# Main2.net
KiCad netlist of a schematic drawn in EAGLE
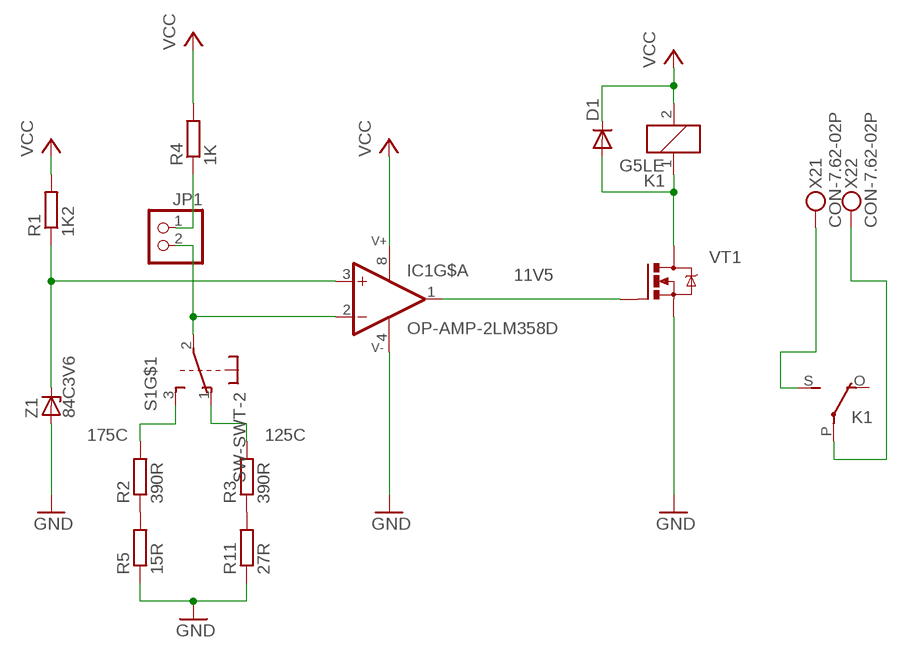
[diagram p0: schematic, sheet 1]
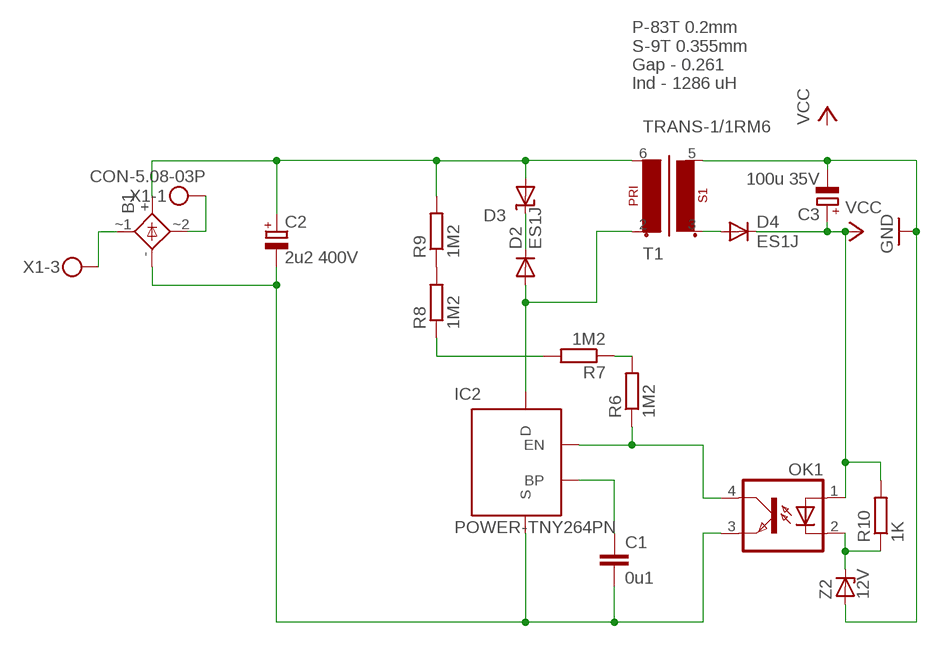
[diagram p1: schematic, sheet 2]

(export (version "E")
  (design (tool "Eeschema 10.0.6"))
  (components
    (comp (ref "D1")
      (value "DIODE_ES1J")
      (footprint "eagle-import:DO214AC")
      (libsource (lib "eagle-import") (part "DIODE_ES1J"))
    )
    (comp (ref "IC1")
      (value "OP-AMP-2LM358D")
      (footprint "eagle-import:SO8")
      (libsource (lib "eagle-import") (part "OP-AMP-2LM358D"))
    )
    (comp (ref "JP1")
      (value "PINHD-1X2")
      (footprint "eagle-import:1X02")
      (libsource (lib "eagle-import") (part "PINHD-1X2"))
    )
    (comp (ref "K1")
      (value "G5LE")
      (footprint "eagle-import:G5LE")
      (libsource (lib "eagle-import") (part "G5LE"))
    )
    (comp (ref "R1")
      (value "1K2")
      (footprint "eagle-import:R1206")
      (libsource (lib "eagle-import") (part "R_1206"))
    )
    (comp (ref "R2")
      (value "390R")
      (footprint "eagle-import:R0805")
      (libsource (lib "eagle-import") (part "R_0805"))
    )
    (comp (ref "R3")
      (value "390R")
      (footprint "eagle-import:R0805")
      (libsource (lib "eagle-import") (part "R_0805"))
    )
    (comp (ref "R4")
      (value "1K")
      (footprint "eagle-import:R1206")
      (libsource (lib "eagle-import") (part "R_1206"))
    )
    (comp (ref "R5")
      (value "15R")
      (footprint "eagle-import:R0805")
      (libsource (lib "eagle-import") (part "R_0805"))
    )
    (comp (ref "R11")
      (value "27R")
      (footprint "eagle-import:R0805")
      (libsource (lib "eagle-import") (part "R_0805"))
    )
    (comp (ref "S1")
      (value "SW-SWT-2")
      (footprint "eagle-import:SWT-2")
      (libsource (lib "eagle-import") (part "SW-SWT-2"))
    )
    (comp (ref "VT1")
      (value "FET-NPF-2X2")
      (footprint "eagle-import:POWERFLAT-2X2")
      (libsource (lib "eagle-import") (part "FET-NPF-2X2"))
    )
    (comp (ref "X2")
      (value "CON-7.62-02P")
      (footprint "eagle-import:KF25C-7.62-02P-13")
      (libsource (lib "eagle-import") (part "CON-7.62-02P"))
    )
    (comp (ref "Z1")
      (value "84C3V6")
      (footprint "eagle-import:SOT23")
      (libsource (lib "eagle-import") (part "ZENER_SOT23"))
    )
    (comp (ref "B1")
      (value "RECTIFIERSOIC-8")
      (footprint "eagle-import:SOIC-4")
      (libsource (lib "eagle-import") (part "RECTIFIERSOIC-8"))
    )
    (comp (ref "C1")
      (value "0u1")
      (footprint "eagle-import:C0805")
      (libsource (lib "eagle-import") (part "CAP_0805"))
    )
    (comp (ref "C2")
      (value "2u2 400V")
      (footprint "eagle-import:E2,5-7")
      (libsource (lib "eagle-import") (part "CAP-POL_E2.5-7"))
    )
    (comp (ref "C3")
      (value "100u 35V")
      (footprint "eagle-import:E3,5-8")
      (libsource (lib "eagle-import") (part "CAP-POL_E3.5-8"))
    )
    (comp (ref "D2")
      (value "ES1J")
      (footprint "eagle-import:DO214AC")
      (libsource (lib "eagle-import") (part "DIODE_ES1J"))
    )
    (comp (ref "D3")
      (value "SUPRESSORDO-204AC")
      (footprint "eagle-import:DO15-12")
      (libsource (lib "eagle-import") (part "SUPRESSORDO-204AC"))
    )
    (comp (ref "D4")
      (value "ES1J")
      (footprint "eagle-import:DO214AC")
      (libsource (lib "eagle-import") (part "DIODE_ES1J"))
    )
    (comp (ref "IC2")
      (value "POWER-TNY264PN")
      (footprint "eagle-import:DIP-8B")
      (libsource (lib "eagle-import") (part "POWER-TNY264PN"))
    )
    (comp (ref "OK1")
      (value "OPTOTRANSPC817")
      (footprint "eagle-import:DIL04")
      (fields (field (name "MPN") "PC817X4J000F"))
      (libsource (lib "eagle-import") (part "OPTOTRANSPC817"))
    )
    (comp (ref "R6")
      (value "1M2")
      (footprint "eagle-import:R0805")
      (libsource (lib "eagle-import") (part "R_0805"))
    )
    (comp (ref "R7")
      (value "1M2")
      (footprint "eagle-import:R0805")
      (libsource (lib "eagle-import") (part "R_0805"))
    )
    (comp (ref "R8")
      (value "1M2")
      (footprint "eagle-import:R0805")
      (libsource (lib "eagle-import") (part "R_0805"))
    )
    (comp (ref "R9")
      (value "1M2")
      (footprint "eagle-import:R0805")
      (libsource (lib "eagle-import") (part "R_0805"))
    )
    (comp (ref "R10")
      (value "1K")
      (footprint "eagle-import:R1206")
      (libsource (lib "eagle-import") (part "R_1206"))
    )
    (comp (ref "T1")
      (value "TRANS-1/1RM6")
      (footprint "eagle-import:RM6")
      (libsource (lib "eagle-import") (part "TRANS-1/1RM6"))
    )
    (comp (ref "X1")
      (value "CON-5.08-03P")
      (footprint "eagle-import:MKDSN1,5_3-5,08")
      (libsource (lib "eagle-import") (part "CON-5.08-03P"))
    )
    (comp (ref "Z2")
      (value "12V")
      (footprint "eagle-import:MINIMELF")
      (libsource (lib "eagle-import") (part "ZENER_MINIMELF"))
    )
  )
  (nets
    (net (code "1") (name "GND") (class "Default")
      (node (ref "C3") (pin "-") (pinfunction "-_-") (pintype "passive"))
      (node (ref "IC1") (pin "4") (pinfunction "V-_4") (pintype "power_in"))
      (node (ref "R11") (pin "1") (pinfunction "1_1") (pintype "passive"))
      (node (ref "R5") (pin "1") (pinfunction "1_1") (pintype "passive"))
      (node (ref "T1") (pin "5") (pinfunction "S1-2_5") (pintype "passive"))
      (node (ref "VT1") (pin "S") (pinfunction "S_S") (pintype "passive"))
      (node (ref "VT1") (pin "S4") (pinfunction "S_S4") (pintype "passive"))
      (node (ref "Z1") (pin "1") (pinfunction "A_1") (pintype "passive"))
      (node (ref "Z2") (pin "A") (pinfunction "A_A") (pintype "passive"))
    )
    (net (code "2") (name "Net-(B1-AC1)") (class "Default")
      (node (ref "B1") (pin "~1") (pinfunction "AC1_~1") (pintype "passive"))
      (node (ref "X1") (pin "3") (pinfunction "KL_3") (pintype "passive"))
    )
    (net (code "3") (name "Net-(B1-AC2)") (class "Default")
      (node (ref "B1") (pin "~2") (pinfunction "AC2_~2") (pintype "passive"))
      (node (ref "X1") (pin "1") (pinfunction "KL_1") (pintype "passive"))
    )
    (net (code "4") (name "Net-(D1-PadA)") (class "Default")
      (node (ref "D1") (pin "A") (pinfunction "A_A") (pintype "passive"))
      (node (ref "K1") (pin "1") (pinfunction "1_1") (pintype "passive"))
      (node (ref "VT1") (pin "D") (pinfunction "D_D") (pintype "passive"))
      (node (ref "VT1") (pin "D1") (pinfunction "D_D1") (pintype "passive"))
      (node (ref "VT1") (pin "D2") (pinfunction "D_D2") (pintype "passive"))
      (node (ref "VT1") (pin "D5") (pinfunction "D_D5") (pintype "passive"))
      (node (ref "VT1") (pin "D6") (pinfunction "D_D6") (pintype "passive"))
    )
    (net (code "5") (name "Net-(D2-PadC)") (class "Default")
      (node (ref "D2") (pin "C") (pinfunction "C_C") (pintype "passive"))
      (node (ref "D3") (pin "C") (pinfunction "C_C") (pintype "passive"))
    )
    (net (code "6") (name "Net-(IC1A-+IN)") (class "Default")
      (node (ref "IC1") (pin "3") (pinfunction "+IN_3") (pintype "input"))
      (node (ref "R1") (pin "1") (pinfunction "1_1") (pintype "passive"))
      (node (ref "Z1") (pin "3") (pinfunction "C_3") (pintype "passive"))
    )
    (net (code "7") (name "Net-(IC1A--IN)") (class "Default")
      (node (ref "IC1") (pin "2") (pinfunction "-IN_2") (pintype "input"))
      (node (ref "JP1") (pin "2") (pinfunction "2_2") (pintype "passive"))
      (node (ref "S1") (pin "2") (pinfunction "2_2") (pintype "passive"))
    )
    (net (code "8") (name "Net-(IC1A-OUT)") (class "Default")
      (node (ref "IC1") (pin "1") (pinfunction "OUT_1") (pintype "output"))
      (node (ref "VT1") (pin "G3") (pinfunction "G_G3") (pintype "passive"))
    )
    (net (code "9") (name "Net-(IC2-BP)") (class "Default")
      (node (ref "C1") (pin "1") (pinfunction "1_1") (pintype "passive"))
      (node (ref "IC2") (pin "1") (pinfunction "BP_1") (pintype "input"))
    )
    (net (code "10") (name "Net-(IC2-D)") (class "Default")
      (node (ref "D2") (pin "A") (pinfunction "A_A") (pintype "passive"))
      (node (ref "IC2") (pin "5") (pinfunction "D_5") (pintype "input"))
      (node (ref "T1") (pin "2") (pinfunction "P1-1_2") (pintype "passive"))
    )
    (net (code "11") (name "Net-(IC2-EN)") (class "Default")
      (node (ref "IC2") (pin "4") (pinfunction "EN_4") (pintype "input"))
      (node (ref "OK1") (pin "4") (pinfunction "COL_4") (pintype "passive"))
      (node (ref "R6") (pin "1") (pinfunction "1_1") (pintype "passive"))
    )
    (net (code "12") (name "Net-(JP1-Pad1)") (class "Default")
      (node (ref "JP1") (pin "1") (pinfunction "1_1") (pintype "passive"))
      (node (ref "R4") (pin "1") (pinfunction "1_1") (pintype "passive"))
    )
    (net (code "13") (name "Net-(OK1-C)") (class "Default")
      (node (ref "OK1") (pin "2") (pinfunction "C_2") (pintype "passive"))
      (node (ref "R10") (pin "1") (pinfunction "1_1") (pintype "passive"))
      (node (ref "Z2") (pin "C") (pinfunction "C_C") (pintype "passive"))
    )
    (net (code "14") (name "Net-(OK1-EMIT)") (class "Default")
      (node (ref "B1") (pin "-") (pinfunction "-_-") (pintype "passive"))
      (node (ref "C1") (pin "2") (pinfunction "2_2") (pintype "passive"))
      (node (ref "C2") (pin "-") (pinfunction "-_-") (pintype "passive"))
      (node (ref "IC2") (pin "2") (pinfunction "S_2") (pintype "input"))
      (node (ref "IC2") (pin "3") (pinfunction "S_3") (pintype "input"))
      (node (ref "IC2") (pin "7") (pinfunction "S_7") (pintype "input"))
      (node (ref "IC2") (pin "8") (pinfunction "S_8") (pintype "input"))
      (node (ref "OK1") (pin "3") (pinfunction "EMIT_3") (pintype "passive"))
    )
    (net (code "15") (name "Net-(R2-Pad1)") (class "Default")
      (node (ref "R2") (pin "1") (pinfunction "1_1") (pintype "passive"))
      (node (ref "R5") (pin "2") (pinfunction "2_2") (pintype "passive"))
    )
    (net (code "16") (name "Net-(R2-Pad2)") (class "Default")
      (node (ref "R2") (pin "2") (pinfunction "2_2") (pintype "passive"))
      (node (ref "S1") (pin "3") (pinfunction "3_3") (pintype "passive"))
    )
    (net (code "17") (name "Net-(R3-Pad2)") (class "Default")
      (node (ref "R3") (pin "2") (pinfunction "2_2") (pintype "passive"))
      (node (ref "S1") (pin "1") (pinfunction "1_1") (pintype "passive"))
    )
    (net (code "18") (name "Net-(R6-Pad2)") (class "Default")
      (node (ref "R6") (pin "2") (pinfunction "2_2") (pintype "passive"))
      (node (ref "R7") (pin "1") (pinfunction "1_1") (pintype "passive"))
    )
    (net (code "19") (name "Net-(R7-Pad2)") (class "Default")
      (node (ref "R7") (pin "2") (pinfunction "2_2") (pintype "passive"))
      (node (ref "R8") (pin "1") (pinfunction "1_1") (pintype "passive"))
    )
    (net (code "20") (name "Net-(R8-Pad2)") (class "Default")
      (node (ref "R8") (pin "2") (pinfunction "2_2") (pintype "passive"))
      (node (ref "R9") (pin "1") (pinfunction "1_1") (pintype "passive"))
    )
    (net (code "21") (name "Net-(R11-Pad2)") (class "Default")
      (node (ref "R11") (pin "2") (pinfunction "2_2") (pintype "passive"))
      (node (ref "R3") (pin "1") (pinfunction "1_1") (pintype "passive"))
    )
    (net (code "22") (name "Net-(T1-P1-2)") (class "Default")
      (node (ref "B1") (pin "+") (pinfunction "+_+") (pintype "passive"))
      (node (ref "C2") (pin "+") (pinfunction "+_+") (pintype "passive"))
      (node (ref "D3") (pin "A") (pinfunction "A_A") (pintype "passive"))
      (node (ref "R9") (pin "2") (pinfunction "2_2") (pintype "passive"))
      (node (ref "T1") (pin "6") (pinfunction "P1-2_6") (pintype "passive"))
    )
    (net (code "23") (name "Net-(T1-S1-1)") (class "Default")
      (node (ref "D4") (pin "A") (pinfunction "A_A") (pintype "passive"))
      (node (ref "T1") (pin "3") (pinfunction "S1-1_3") (pintype "passive"))
    )
    (net (code "24") (name "Net-(X2A-KL)") (class "Default")
      (node (ref "K1") (pin "S") (pinfunction "S_S") (pintype "passive"))
      (node (ref "X2") (pin "P$1") (pinfunction "KL_P$1") (pintype "passive"))
    )
    (net (code "25") (name "Net-(X2B-KL)") (class "Default")
      (node (ref "K1") (pin "P") (pinfunction "P_P") (pintype "passive"))
      (node (ref "X2") (pin "P$2") (pinfunction "KL_P$2") (pintype "passive"))
    )
    (net (code "26") (name "VCC") (class "Default")
      (node (ref "C3") (pin "+") (pinfunction "+_+") (pintype "passive"))
      (node (ref "D1") (pin "C") (pinfunction "C_C") (pintype "passive"))
      (node (ref "D4") (pin "C") (pinfunction "C_C") (pintype "passive"))
      (node (ref "IC1") (pin "8") (pinfunction "V+_8") (pintype "power_in"))
      (node (ref "K1") (pin "2") (pinfunction "2_2") (pintype "passive"))
      (node (ref "OK1") (pin "1") (pinfunction "A_1") (pintype "passive"))
      (node (ref "R1") (pin "2") (pinfunction "2_2") (pintype "passive"))
      (node (ref "R10") (pin "2") (pinfunction "2_2") (pintype "passive"))
      (node (ref "R4") (pin "2") (pinfunction "2_2") (pintype "passive"))
    )
    (net (code "27") (name "unconnected-(K1-PadO)") (class "Default")
      (node (ref "K1") (pin "O") (pinfunction "O_O") (pintype "passive"))
    )
  )
)
